# Communication.net
KiCad netlist of a schematic drawn in EAGLE
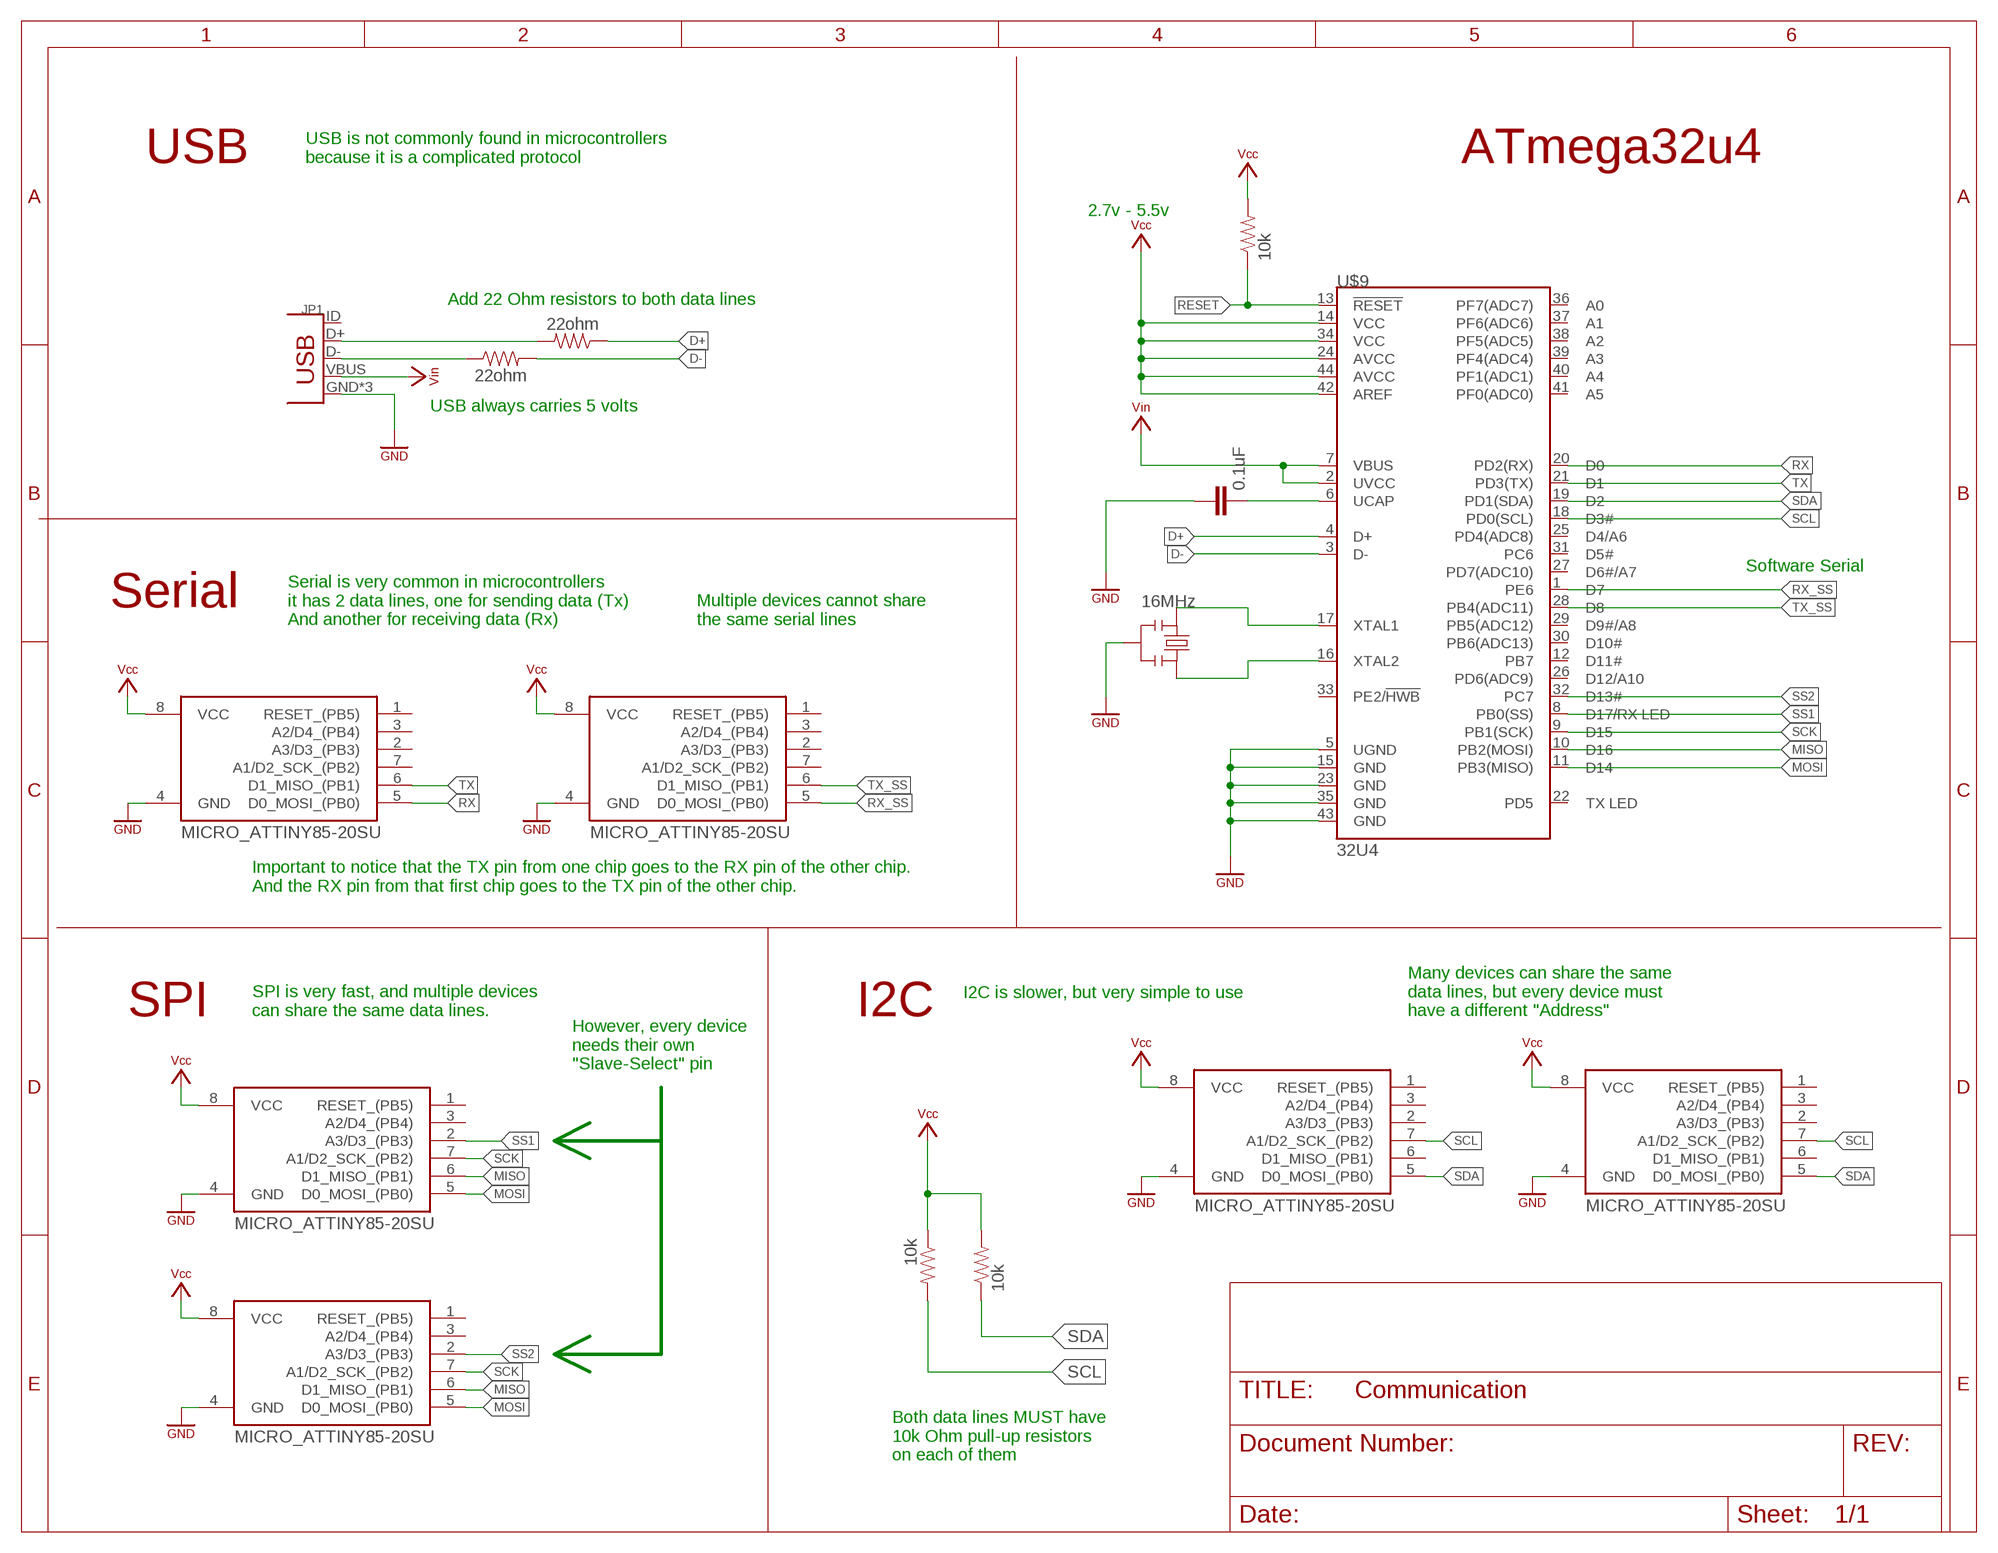
[diagram p0: schematic, sheet 1]

(export (version "E")
  (design (tool "Eeschema 10.0.6"))
  (components
    (comp (ref "C1")
      (value "0.1uF")
      (footprint "eagle-import:0805")
      (libsource (lib "eagle-import") (part "COMPONENT_CAP-0805"))
    )
    (comp (ref "JP1")
      (value "CONN_USB-10118192-0001LF")
      (footprint "eagle-import:USB-MICRO-FEMALE")
      (libsource (lib "eagle-import") (part "CONN_USB-10118192-0001LF"))
    )
    (comp (ref "R6")
      (value "22ohm")
      (footprint "eagle-import:0805")
      (libsource (lib "eagle-import") (part "COMPONENT_RESISTOR-0805"))
    )
    (comp (ref "R7")
      (value "22ohm")
      (footprint "eagle-import:0805")
      (libsource (lib "eagle-import") (part "COMPONENT_RESISTOR-0805"))
    )
    (comp (ref "R8")
      (value "10k")
      (footprint "eagle-import:0805")
      (libsource (lib "eagle-import") (part "COMPONENT_RESISTOR-0805"))
    )
    (comp (ref "R9")
      (value "10k")
      (footprint "eagle-import:0805")
      (libsource (lib "eagle-import") (part "COMPONENT_RESISTOR-0805"))
    )
    (comp (ref "R10")
      (value "10k")
      (footprint "eagle-import:0805")
      (libsource (lib "eagle-import") (part "COMPONENT_RESISTOR-0805"))
    )
    (comp (ref "U$3")
      (value "MICRO_ATTINY85-20SU")
      (footprint "eagle-import:SOIC8")
      (libsource (lib "eagle-import") (part "MICRO_ATTINY85-20SU"))
    )
    (comp (ref "U$4")
      (value "MICRO_ATTINY85-20SU")
      (footprint "eagle-import:SOIC8")
      (libsource (lib "eagle-import") (part "MICRO_ATTINY85-20SU"))
    )
    (comp (ref "U$5")
      (value "MICRO_ATTINY85-20SU")
      (footprint "eagle-import:SOIC8")
      (libsource (lib "eagle-import") (part "MICRO_ATTINY85-20SU"))
    )
    (comp (ref "U$6")
      (value "MICRO_ATTINY85-20SU")
      (footprint "eagle-import:SOIC8")
      (libsource (lib "eagle-import") (part "MICRO_ATTINY85-20SU"))
    )
    (comp (ref "U$7")
      (value "MICRO_ATTINY85-20SU")
      (footprint "eagle-import:SOIC8")
      (libsource (lib "eagle-import") (part "MICRO_ATTINY85-20SU"))
    )
    (comp (ref "U$8")
      (value "MICRO_ATTINY85-20SU")
      (footprint "eagle-import:SOIC8")
      (libsource (lib "eagle-import") (part "MICRO_ATTINY85-20SU"))
    )
    (comp (ref "U$9")
      (value "32U4")
      (footprint "eagle-import:TQFP44")
      (libsource (lib "eagle-import") (part "MICRO_ATMEGA32U4TQFP-44"))
    )
    (comp (ref "Y2")
      (value "16MHz")
      (footprint "eagle-import:RESONATOR-SMD")
      (libsource (lib "eagle-import") (part "COMPONENT_RESONATOR-1.2MM-PITCH"))
    )
  )
  (nets
    (net (code "1") (name "D+") (class "Default")
      (node (ref "R7") (pin "1") (pinfunction "1_1") (pintype "passive"))
      (node (ref "U$9") (pin "4") (pinfunction "D+_4") (pintype "bidirectional"))
    )
    (net (code "2") (name "D-") (class "Default")
      (node (ref "R6") (pin "2") (pinfunction "2_2") (pintype "passive"))
      (node (ref "U$9") (pin "3") (pinfunction "D-_3") (pintype "bidirectional"))
    )
    (net (code "3") (name "MISO") (class "Default")
      (node (ref "U$3") (pin "6") (pinfunction "D1_MISO_(PB1)_6") (pintype "bidirectional"))
      (node (ref "U$4") (pin "6") (pinfunction "D1_MISO_(PB1)_6") (pintype "bidirectional"))
      (node (ref "U$9") (pin "10") (pinfunction "PB2(MOSI)_10") (pintype "bidirectional"))
    )
    (net (code "4") (name "MOSI") (class "Default")
      (node (ref "U$3") (pin "5") (pinfunction "D0_MOSI_(PB0)_5") (pintype "bidirectional"))
      (node (ref "U$4") (pin "5") (pinfunction "D0_MOSI_(PB0)_5") (pintype "bidirectional"))
      (node (ref "U$9") (pin "11") (pinfunction "PB3(MISO)_11") (pintype "bidirectional"))
    )
    (net (code "5") (name "Net-(JP1-PadD+)") (class "Default")
      (node (ref "JP1") (pin "D+") (pinfunction "D+_D+") (pintype "bidirectional"))
      (node (ref "R7") (pin "2") (pinfunction "2_2") (pintype "passive"))
    )
    (net (code "6") (name "Net-(JP1-PadD-)") (class "Default")
      (node (ref "JP1") (pin "D-") (pinfunction "D-_D-") (pintype "bidirectional"))
      (node (ref "R6") (pin "1") (pinfunction "1_1") (pintype "passive"))
    )
    (net (code "7") (name "Net-(U$9-UCAP)") (class "Default")
      (node (ref "C1") (pin "2") (pinfunction "2_2") (pintype "passive"))
      (node (ref "U$9") (pin "6") (pinfunction "UCAP_6") (pintype "bidirectional"))
    )
    (net (code "8") (name "Net-(U$9-XTAL1)") (class "Default")
      (node (ref "U$9") (pin "17") (pinfunction "XTAL1_17") (pintype "bidirectional"))
      (node (ref "Y2") (pin "1") (pinfunction "1_1") (pintype "passive"))
    )
    (net (code "9") (name "Net-(U$9-XTAL2)") (class "Default")
      (node (ref "U$9") (pin "16") (pinfunction "XTAL2_16") (pintype "bidirectional"))
      (node (ref "Y2") (pin "3") (pinfunction "3_3") (pintype "passive"))
    )
    (net (code "10") (name "RESET") (class "Default")
      (node (ref "R10") (pin "1") (pinfunction "1_1") (pintype "passive"))
      (node (ref "U$9") (pin "13") (pinfunction "~{RESET}_13") (pintype "bidirectional"))
    )
    (net (code "11") (name "RX") (class "Default")
      (node (ref "U$7") (pin "5") (pinfunction "D0_MOSI_(PB0)_5") (pintype "bidirectional"))
      (node (ref "U$9") (pin "20") (pinfunction "PD2(RX)_20") (pintype "bidirectional"))
    )
    (net (code "12") (name "RX_SS") (class "Default")
      (node (ref "U$8") (pin "5") (pinfunction "D0_MOSI_(PB0)_5") (pintype "bidirectional"))
      (node (ref "U$9") (pin "1") (pinfunction "PE6_1") (pintype "bidirectional"))
    )
    (net (code "13") (name "SCK") (class "Default")
      (node (ref "U$3") (pin "7") (pinfunction "A1/D2_SCK_(PB2)_7") (pintype "bidirectional"))
      (node (ref "U$4") (pin "7") (pinfunction "A1/D2_SCK_(PB2)_7") (pintype "bidirectional"))
      (node (ref "U$9") (pin "9") (pinfunction "PB1(SCK)_9") (pintype "bidirectional"))
    )
    (net (code "14") (name "SCL") (class "Default")
      (node (ref "R8") (pin "2") (pinfunction "2_2") (pintype "passive"))
      (node (ref "U$5") (pin "7") (pinfunction "A1/D2_SCK_(PB2)_7") (pintype "bidirectional"))
      (node (ref "U$6") (pin "7") (pinfunction "A1/D2_SCK_(PB2)_7") (pintype "bidirectional"))
      (node (ref "U$9") (pin "18") (pinfunction "PD0(SCL)_18") (pintype "bidirectional"))
    )
    (net (code "15") (name "SDA") (class "Default")
      (node (ref "R9") (pin "1") (pinfunction "1_1") (pintype "passive"))
      (node (ref "U$5") (pin "5") (pinfunction "D0_MOSI_(PB0)_5") (pintype "bidirectional"))
      (node (ref "U$6") (pin "5") (pinfunction "D0_MOSI_(PB0)_5") (pintype "bidirectional"))
      (node (ref "U$9") (pin "19") (pinfunction "PD1(SDA)_19") (pintype "bidirectional"))
    )
    (net (code "16") (name "SS1") (class "Default")
      (node (ref "U$3") (pin "2") (pinfunction "A3/D3_(PB3)_2") (pintype "bidirectional"))
      (node (ref "U$9") (pin "8") (pinfunction "PB0(SS)_8") (pintype "bidirectional"))
    )
    (net (code "17") (name "SS2") (class "Default")
      (node (ref "U$4") (pin "2") (pinfunction "A3/D3_(PB3)_2") (pintype "bidirectional"))
      (node (ref "U$9") (pin "32") (pinfunction "PC7_32") (pintype "bidirectional"))
    )
    (net (code "18") (name "SYMBOL_GND") (class "Default")
      (node (ref "C1") (pin "1") (pinfunction "1_1") (pintype "passive"))
      (node (ref "JP1") (pin "GND") (pinfunction "GND_GND") (pintype "bidirectional"))
      (node (ref "JP1") (pin "MT1") (pinfunction "GND_MT1") (pintype "bidirectional"))
      (node (ref "JP1") (pin "MT2") (pinfunction "GND_MT2") (pintype "bidirectional"))
      (node (ref "U$3") (pin "4") (pinfunction "GND_4") (pintype "power_in"))
      (node (ref "U$4") (pin "4") (pinfunction "GND_4") (pintype "power_in"))
      (node (ref "U$5") (pin "4") (pinfunction "GND_4") (pintype "power_in"))
      (node (ref "U$6") (pin "4") (pinfunction "GND_4") (pintype "power_in"))
      (node (ref "U$7") (pin "4") (pinfunction "GND_4") (pintype "power_in"))
      (node (ref "U$8") (pin "4") (pinfunction "GND_4") (pintype "power_in"))
      (node (ref "U$9") (pin "15") (pinfunction "GND_15") (pintype "bidirectional"))
      (node (ref "U$9") (pin "23") (pinfunction "GND_23") (pintype "bidirectional"))
      (node (ref "U$9") (pin "35") (pinfunction "GND_35") (pintype "bidirectional"))
      (node (ref "U$9") (pin "43") (pinfunction "GND_43") (pintype "bidirectional"))
      (node (ref "U$9") (pin "5") (pinfunction "UGND_5") (pintype "bidirectional"))
      (node (ref "Y2") (pin "2") (pinfunction "2_2") (pintype "passive"))
    )
    (net (code "19") (name "SYMBOL_VCC") (class "Default")
      (node (ref "R10") (pin "2") (pinfunction "2_2") (pintype "passive"))
      (node (ref "R8") (pin "1") (pinfunction "1_1") (pintype "passive"))
      (node (ref "R9") (pin "2") (pinfunction "2_2") (pintype "passive"))
      (node (ref "U$3") (pin "8") (pinfunction "VCC_8") (pintype "power_in"))
      (node (ref "U$4") (pin "8") (pinfunction "VCC_8") (pintype "power_in"))
      (node (ref "U$5") (pin "8") (pinfunction "VCC_8") (pintype "power_in"))
      (node (ref "U$6") (pin "8") (pinfunction "VCC_8") (pintype "power_in"))
      (node (ref "U$7") (pin "8") (pinfunction "VCC_8") (pintype "power_in"))
      (node (ref "U$8") (pin "8") (pinfunction "VCC_8") (pintype "power_in"))
      (node (ref "U$9") (pin "14") (pinfunction "VCC_14") (pintype "bidirectional"))
      (node (ref "U$9") (pin "24") (pinfunction "AVCC_24") (pintype "bidirectional"))
      (node (ref "U$9") (pin "34") (pinfunction "VCC_34") (pintype "bidirectional"))
      (node (ref "U$9") (pin "42") (pinfunction "AREF_42") (pintype "bidirectional"))
      (node (ref "U$9") (pin "44") (pinfunction "AVCC_44") (pintype "bidirectional"))
    )
    (net (code "20") (name "SYMBOL_VIN") (class "Default")
      (node (ref "JP1") (pin "VBUS") (pinfunction "VBUS_VBUS") (pintype "bidirectional"))
      (node (ref "U$9") (pin "2") (pinfunction "UVCC_2") (pintype "bidirectional"))
      (node (ref "U$9") (pin "7") (pinfunction "VBUS_7") (pintype "bidirectional"))
    )
    (net (code "21") (name "TX") (class "Default")
      (node (ref "U$7") (pin "6") (pinfunction "D1_MISO_(PB1)_6") (pintype "bidirectional"))
      (node (ref "U$9") (pin "21") (pinfunction "PD3(TX)_21") (pintype "bidirectional"))
    )
    (net (code "22") (name "TX_SS") (class "Default")
      (node (ref "U$8") (pin "6") (pinfunction "D1_MISO_(PB1)_6") (pintype "bidirectional"))
      (node (ref "U$9") (pin "28") (pinfunction "PB4(ADC11)_28") (pintype "bidirectional"))
    )
    (net (code "23") (name "unconnected-(JP1-SHIELD-PadID)") (class "Default")
      (node (ref "JP1") (pin "ID") (pinfunction "SHIELD_ID") (pintype "bidirectional"))
    )
    (net (code "24") (name "unconnected-(U$3-A2{slash}D4_(PB4)-Pad3)") (class "Default")
      (node (ref "U$3") (pin "3") (pinfunction "A2/D4_(PB4)_3") (pintype "bidirectional"))
    )
    (net (code "25") (name "unconnected-(U$3-RESET_(PB5)-Pad1)") (class "Default")
      (node (ref "U$3") (pin "1") (pinfunction "RESET_(PB5)_1") (pintype "bidirectional"))
    )
    (net (code "26") (name "unconnected-(U$4-A2{slash}D4_(PB4)-Pad3)") (class "Default")
      (node (ref "U$4") (pin "3") (pinfunction "A2/D4_(PB4)_3") (pintype "bidirectional"))
    )
    (net (code "27") (name "unconnected-(U$4-RESET_(PB5)-Pad1)") (class "Default")
      (node (ref "U$4") (pin "1") (pinfunction "RESET_(PB5)_1") (pintype "bidirectional"))
    )
    (net (code "28") (name "unconnected-(U$5-A2{slash}D4_(PB4)-Pad3)") (class "Default")
      (node (ref "U$5") (pin "3") (pinfunction "A2/D4_(PB4)_3") (pintype "bidirectional"))
    )
    (net (code "29") (name "unconnected-(U$5-A3{slash}D3_(PB3)-Pad2)") (class "Default")
      (node (ref "U$5") (pin "2") (pinfunction "A3/D3_(PB3)_2") (pintype "bidirectional"))
    )
    (net (code "30") (name "unconnected-(U$5-D1_MISO_(PB1)-Pad6)") (class "Default")
      (node (ref "U$5") (pin "6") (pinfunction "D1_MISO_(PB1)_6") (pintype "bidirectional"))
    )
    (net (code "31") (name "unconnected-(U$5-RESET_(PB5)-Pad1)") (class "Default")
      (node (ref "U$5") (pin "1") (pinfunction "RESET_(PB5)_1") (pintype "bidirectional"))
    )
    (net (code "32") (name "unconnected-(U$6-A2{slash}D4_(PB4)-Pad3)") (class "Default")
      (node (ref "U$6") (pin "3") (pinfunction "A2/D4_(PB4)_3") (pintype "bidirectional"))
    )
    (net (code "33") (name "unconnected-(U$6-A3{slash}D3_(PB3)-Pad2)") (class "Default")
      (node (ref "U$6") (pin "2") (pinfunction "A3/D3_(PB3)_2") (pintype "bidirectional"))
    )
    (net (code "34") (name "unconnected-(U$6-D1_MISO_(PB1)-Pad6)") (class "Default")
      (node (ref "U$6") (pin "6") (pinfunction "D1_MISO_(PB1)_6") (pintype "bidirectional"))
    )
    (net (code "35") (name "unconnected-(U$6-RESET_(PB5)-Pad1)") (class "Default")
      (node (ref "U$6") (pin "1") (pinfunction "RESET_(PB5)_1") (pintype "bidirectional"))
    )
    (net (code "36") (name "unconnected-(U$7-A1{slash}D2_SCK_(PB2)-Pad7)") (class "Default")
      (node (ref "U$7") (pin "7") (pinfunction "A1/D2_SCK_(PB2)_7") (pintype "bidirectional"))
    )
    (net (code "37") (name "unconnected-(U$7-A2{slash}D4_(PB4)-Pad3)") (class "Default")
      (node (ref "U$7") (pin "3") (pinfunction "A2/D4_(PB4)_3") (pintype "bidirectional"))
    )
    (net (code "38") (name "unconnected-(U$7-A3{slash}D3_(PB3)-Pad2)") (class "Default")
      (node (ref "U$7") (pin "2") (pinfunction "A3/D3_(PB3)_2") (pintype "bidirectional"))
    )
    (net (code "39") (name "unconnected-(U$7-RESET_(PB5)-Pad1)") (class "Default")
      (node (ref "U$7") (pin "1") (pinfunction "RESET_(PB5)_1") (pintype "bidirectional"))
    )
    (net (code "40") (name "unconnected-(U$8-A1{slash}D2_SCK_(PB2)-Pad7)") (class "Default")
      (node (ref "U$8") (pin "7") (pinfunction "A1/D2_SCK_(PB2)_7") (pintype "bidirectional"))
    )
    (net (code "41") (name "unconnected-(U$8-A2{slash}D4_(PB4)-Pad3)") (class "Default")
      (node (ref "U$8") (pin "3") (pinfunction "A2/D4_(PB4)_3") (pintype "bidirectional"))
    )
    (net (code "42") (name "unconnected-(U$8-A3{slash}D3_(PB3)-Pad2)") (class "Default")
      (node (ref "U$8") (pin "2") (pinfunction "A3/D3_(PB3)_2") (pintype "bidirectional"))
    )
    (net (code "43") (name "unconnected-(U$8-RESET_(PB5)-Pad1)") (class "Default")
      (node (ref "U$8") (pin "1") (pinfunction "RESET_(PB5)_1") (pintype "bidirectional"))
    )
    (net (code "44") (name "unconnected-(U$9-PB5(ADC12)-Pad29)") (class "Default")
      (node (ref "U$9") (pin "29") (pinfunction "PB5(ADC12)_29") (pintype "bidirectional"))
    )
    (net (code "45") (name "unconnected-(U$9-PB6(ADC13)-Pad30)") (class "Default")
      (node (ref "U$9") (pin "30") (pinfunction "PB6(ADC13)_30") (pintype "bidirectional"))
    )
    (net (code "46") (name "unconnected-(U$9-PB7-Pad12)") (class "Default")
      (node (ref "U$9") (pin "12") (pinfunction "PB7_12") (pintype "bidirectional"))
    )
    (net (code "47") (name "unconnected-(U$9-PC6-Pad31)") (class "Default")
      (node (ref "U$9") (pin "31") (pinfunction "PC6_31") (pintype "bidirectional"))
    )
    (net (code "48") (name "unconnected-(U$9-PD4(ADC8)-Pad25)") (class "Default")
      (node (ref "U$9") (pin "25") (pinfunction "PD4(ADC8)_25") (pintype "bidirectional"))
    )
    (net (code "49") (name "unconnected-(U$9-PD5-Pad22)") (class "Default")
      (node (ref "U$9") (pin "22") (pinfunction "PD5_22") (pintype "bidirectional"))
    )
    (net (code "50") (name "unconnected-(U$9-PD6(ADC9)-Pad26)") (class "Default")
      (node (ref "U$9") (pin "26") (pinfunction "PD6(ADC9)_26") (pintype "bidirectional"))
    )
    (net (code "51") (name "unconnected-(U$9-PD7(ADC10)-Pad27)") (class "Default")
      (node (ref "U$9") (pin "27") (pinfunction "PD7(ADC10)_27") (pintype "bidirectional"))
    )
    (net (code "52") (name "unconnected-(U$9-PE2{slash}~{HWB}-Pad33)") (class "Default")
      (node (ref "U$9") (pin "33") (pinfunction "PE2/~{HWB}_33") (pintype "bidirectional"))
    )
    (net (code "53") (name "unconnected-(U$9-PF0(ADC0)-Pad41)") (class "Default")
      (node (ref "U$9") (pin "41") (pinfunction "PF0(ADC0)_41") (pintype "bidirectional"))
    )
    (net (code "54") (name "unconnected-(U$9-PF1(ADC1)-Pad40)") (class "Default")
      (node (ref "U$9") (pin "40") (pinfunction "PF1(ADC1)_40") (pintype "bidirectional"))
    )
    (net (code "55") (name "unconnected-(U$9-PF4(ADC4)-Pad39)") (class "Default")
      (node (ref "U$9") (pin "39") (pinfunction "PF4(ADC4)_39") (pintype "bidirectional"))
    )
    (net (code "56") (name "unconnected-(U$9-PF5(ADC5)-Pad38)") (class "Default")
      (node (ref "U$9") (pin "38") (pinfunction "PF5(ADC5)_38") (pintype "bidirectional"))
    )
    (net (code "57") (name "unconnected-(U$9-PF6(ADC6)-Pad37)") (class "Default")
      (node (ref "U$9") (pin "37") (pinfunction "PF6(ADC6)_37") (pintype "bidirectional"))
    )
    (net (code "58") (name "unconnected-(U$9-PF7(ADC7)-Pad36)") (class "Default")
      (node (ref "U$9") (pin "36") (pinfunction "PF7(ADC7)_36") (pintype "bidirectional"))
    )
  )
)
